# ADC.net
KiCad netlist of a schematic drawn in Altium Designer
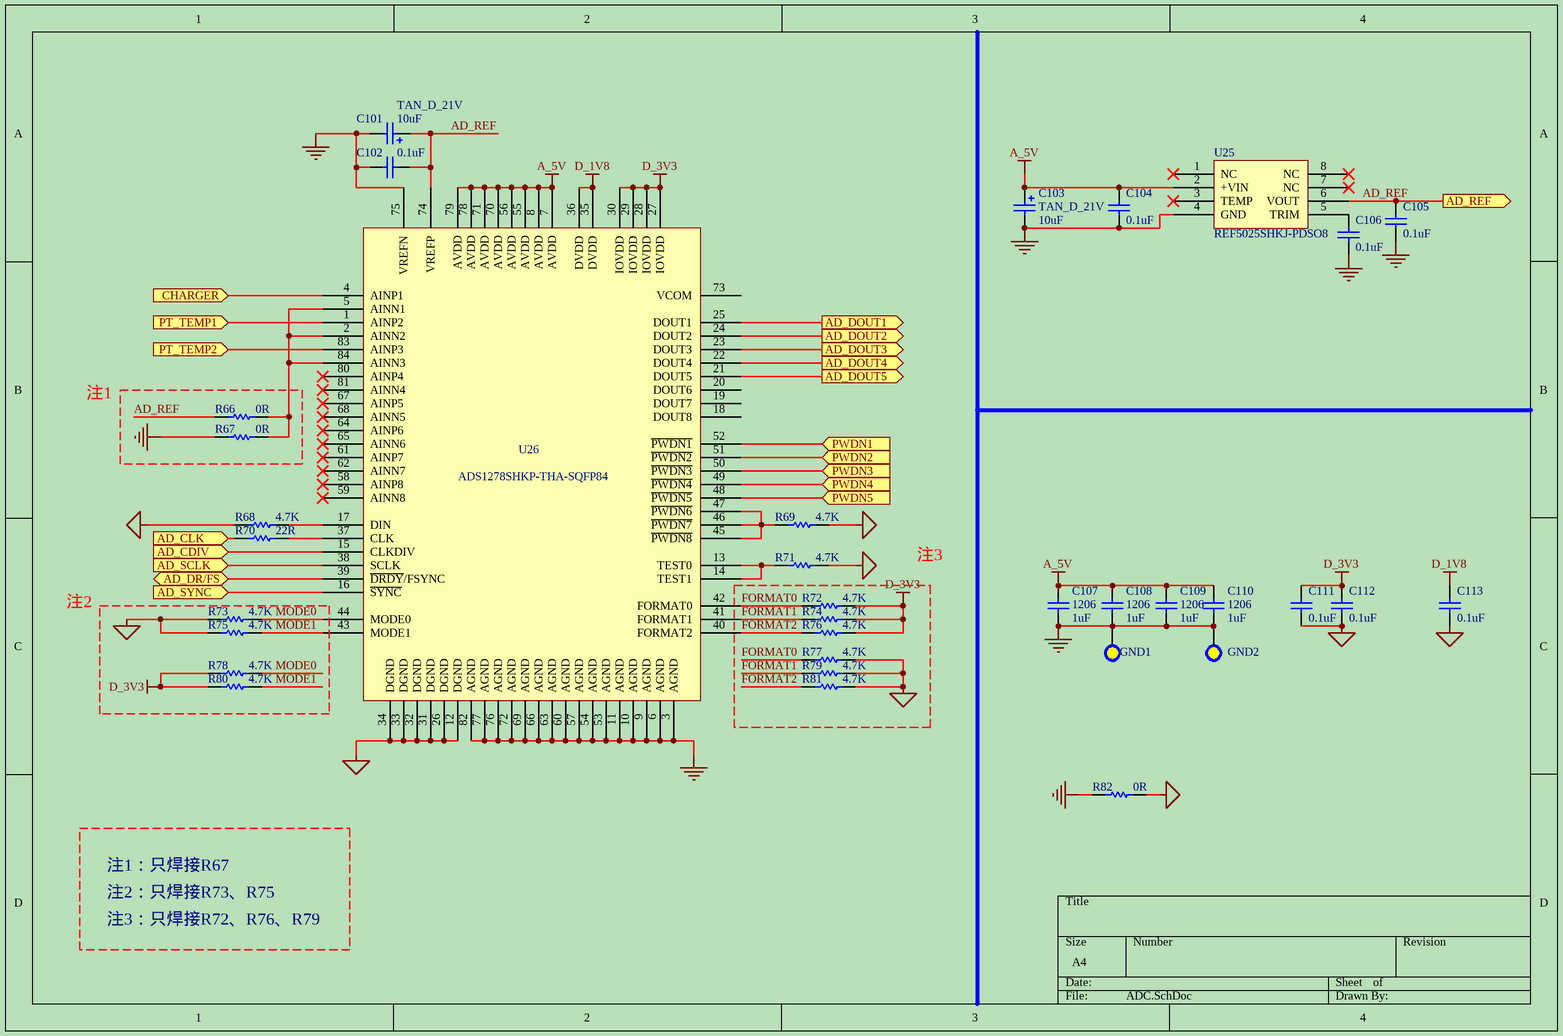
[diagram p0: ADC.SchDoc]

(export (version "E")
  (design (tool "Eeschema 10.0.6"))
  (components
    (comp (ref "C101")
      (value "TAN_D_21V")
      (footprint "EMRT MAIN CONTROLLER:CAPSP_2q2917")
      (description "Polarized Capacitor")
      (fields (field (name "ALTIUM_VALUE") "10uF") (field (name "PART NUMBER") "Y20024818"))
      (libsource (lib "电容") (part "Y20024818"))
    )
    (comp (ref "C102")
      (value "0.1uF")
      (footprint "CAPS0805_57")
      (description "Capacitor")
      (fields (field (name "PART NUMBER") "Y20025084") (field (name "Comment") "Cap"))
      (libsource (lib "Cap") (part "Cap"))
    )
    (comp (ref "C103")
      (value "TAN_D_21V")
      (footprint "EMRT MAIN CONTROLLER:CAPSP_2q2917")
      (description "Polarized Capacitor")
      (fields (field (name "ALTIUM_VALUE") "10uF") (field (name "PART NUMBER") "Y20024818"))
      (libsource (lib "电容") (part "Y20024818"))
    )
    (comp (ref "C104")
      (value "0.1uF")
      (footprint "CAPS0805_57")
      (description "Capacitor")
      (fields (field (name "PART NUMBER") "Y20025084") (field (name "Comment") "Cap"))
      (libsource (lib "Cap") (part "Cap"))
    )
    (comp (ref "C105")
      (value "0.1uF")
      (footprint "CAPS0805_57")
      (description "Capacitor")
      (fields (field (name "PART NUMBER") "Y20025084") (field (name "Comment") "Cap"))
      (libsource (lib "Cap") (part "Cap"))
    )
    (comp (ref "C106")
      (value "0.1uF")
      (footprint "CAPS0805_57")
      (description "Capacitor")
      (fields (field (name "PART NUMBER") "Y20025084") (field (name "Comment") "Cap"))
      (libsource (lib "Cap") (part "Cap"))
    )
    (comp (ref "C107")
      (value "1206")
      (footprint "CAPS1206_43")
      (description "Capacitor")
      (fields (field (name "ALTIUM_VALUE") "1uF") (field (name "PART NUMBER") "Y20024113"))
      (libsource (lib "Cap") (part "Cap"))
    )
    (comp (ref "C108")
      (value "1206")
      (footprint "CAPS1206_43")
      (description "Capacitor")
      (fields (field (name "ALTIUM_VALUE") "1uF") (field (name "PART NUMBER") "Y20024113"))
      (libsource (lib "Cap") (part "Cap"))
    )
    (comp (ref "C109")
      (value "1206")
      (footprint "CAPS1206_43")
      (description "Capacitor")
      (fields (field (name "ALTIUM_VALUE") "1uF") (field (name "PART NUMBER") "Y20024113"))
      (libsource (lib "Cap") (part "Cap"))
    )
    (comp (ref "C110")
      (value "1206")
      (footprint "CAPS1206_43")
      (description "Capacitor")
      (fields (field (name "ALTIUM_VALUE") "1uF") (field (name "PART NUMBER") "Y20024113"))
      (libsource (lib "Cap") (part "Cap"))
    )
    (comp (ref "C111")
      (value "0.1uF")
      (footprint "CAPS0805_57")
      (description "Capacitor")
      (fields (field (name "PART NUMBER") "Y20025084") (field (name "Comment") "Cap"))
      (libsource (lib "Cap") (part "Cap"))
    )
    (comp (ref "C112")
      (value "0.1uF")
      (footprint "CAPS0805_57")
      (description "Capacitor")
      (fields (field (name "PART NUMBER") "Y20025084") (field (name "Comment") "Cap"))
      (libsource (lib "Cap") (part "Cap"))
    )
    (comp (ref "C113")
      (value "0.1uF")
      (footprint "CAPS0805_57")
      (description "Capacitor")
      (fields (field (name "PART NUMBER") "Y20025084") (field (name "Comment") "Cap"))
      (libsource (lib "Cap") (part "Cap"))
    )
    (comp (ref "GND1")
      (value "TST_LARGE")
      (footprint "test_large")
      (libsource (lib "srj") (part "TEST_LARGE"))
    )
    (comp (ref "GND2")
      (value "TST_LARGE")
      (footprint "test_large")
      (libsource (lib "srj") (part "TEST_LARGE"))
    )
    (comp (ref "R66")
      (value "0R")
      (footprint "RESS0805")
      (description "Semiconductor Resistor")
      (fields
        (field (name "MANUFACTURER") "Generic Components")
        (field (name "Comment") "Res")
        (field (name "PUBLISHER") "Altium Hobart Technology Centre")
      )
      (libsource (lib "EMRT MAIN CONTROLLER") (part "Res"))
    )
    (comp (ref "R67")
      (value "0R")
      (footprint "RESS0805")
      (description "Semiconductor Resistor")
      (fields
        (field (name "MANUFACTURER") "Generic Components")
        (field (name "Comment") "Res")
        (field (name "PUBLISHER") "Altium Hobart Technology Centre")
      )
      (libsource (lib "EMRT MAIN CONTROLLER") (part "Res"))
    )
    (comp (ref "R68")
      (value "4.7K")
      (footprint "RESS0805")
      (description "Semiconductor Resistor")
      (fields
        (field (name "MANUFACTURER") "Generic Components")
        (field (name "Comment") "Res")
        (field (name "PUBLISHER") "Altium Hobart Technology Centre")
      )
      (libsource (lib "EMRT MAIN CONTROLLER") (part "Res"))
    )
    (comp (ref "R69")
      (value "4.7K")
      (footprint "RESS0805")
      (description "Semiconductor Resistor")
      (fields
        (field (name "MANUFACTURER") "Generic Components")
        (field (name "Comment") "Res")
        (field (name "PUBLISHER") "Altium Hobart Technology Centre")
      )
      (libsource (lib "EMRT MAIN CONTROLLER") (part "Res"))
    )
    (comp (ref "R70")
      (value "22R")
      (footprint "RESS0805")
      (description "Semiconductor Resistor")
      (fields
        (field (name "MANUFACTURER") "Generic Components")
        (field (name "Comment") "Res")
        (field (name "PUBLISHER") "Altium Hobart Technology Centre")
      )
      (libsource (lib "EMRT MAIN CONTROLLER") (part "Res"))
    )
    (comp (ref "R71")
      (value "4.7K")
      (footprint "RESS0805")
      (description "Semiconductor Resistor")
      (fields
        (field (name "MANUFACTURER") "Generic Components")
        (field (name "Comment") "Res")
        (field (name "PUBLISHER") "Altium Hobart Technology Centre")
      )
      (libsource (lib "EMRT MAIN CONTROLLER") (part "Res"))
    )
    (comp (ref "R72")
      (value "4.7K")
      (footprint "RESS0805")
      (description "Semiconductor Resistor")
      (fields
        (field (name "MANUFACTURER") "Generic Components")
        (field (name "Comment") "Res")
        (field (name "PUBLISHER") "Altium Hobart Technology Centre")
      )
      (libsource (lib "EMRT MAIN CONTROLLER") (part "Res"))
    )
    (comp (ref "R73")
      (value "4.7K")
      (footprint "RESS0805")
      (description "Semiconductor Resistor")
      (fields
        (field (name "MANUFACTURER") "Generic Components")
        (field (name "Comment") "Res")
        (field (name "PUBLISHER") "Altium Hobart Technology Centre")
      )
      (libsource (lib "EMRT MAIN CONTROLLER") (part "Res"))
    )
    (comp (ref "R74")
      (value "4.7K")
      (footprint "RESS0805")
      (description "Semiconductor Resistor")
      (fields
        (field (name "MANUFACTURER") "Generic Components")
        (field (name "Comment") "Res")
        (field (name "PUBLISHER") "Altium Hobart Technology Centre")
      )
      (libsource (lib "EMRT MAIN CONTROLLER") (part "Res"))
    )
    (comp (ref "R75")
      (value "4.7K")
      (footprint "RESS0805")
      (description "Semiconductor Resistor")
      (fields
        (field (name "MANUFACTURER") "Generic Components")
        (field (name "Comment") "Res")
        (field (name "PUBLISHER") "Altium Hobart Technology Centre")
      )
      (libsource (lib "EMRT MAIN CONTROLLER") (part "Res"))
    )
    (comp (ref "R76")
      (value "4.7K")
      (footprint "RESS0805")
      (description "Semiconductor Resistor")
      (fields
        (field (name "MANUFACTURER") "Generic Components")
        (field (name "Comment") "Res")
        (field (name "PUBLISHER") "Altium Hobart Technology Centre")
      )
      (libsource (lib "EMRT MAIN CONTROLLER") (part "Res"))
    )
    (comp (ref "R77")
      (value "4.7K")
      (footprint "RESS0805")
      (description "Semiconductor Resistor")
      (fields
        (field (name "MANUFACTURER") "Generic Components")
        (field (name "Comment") "Res")
        (field (name "PUBLISHER") "Altium Hobart Technology Centre")
      )
      (libsource (lib "EMRT MAIN CONTROLLER") (part "Res"))
    )
    (comp (ref "R78")
      (value "4.7K")
      (footprint "RESS0805")
      (description "Semiconductor Resistor")
      (fields
        (field (name "MANUFACTURER") "Generic Components")
        (field (name "Comment") "Res")
        (field (name "PUBLISHER") "Altium Hobart Technology Centre")
      )
      (libsource (lib "EMRT MAIN CONTROLLER") (part "Res"))
    )
    (comp (ref "R79")
      (value "4.7K")
      (footprint "RESS0805")
      (description "Semiconductor Resistor")
      (fields
        (field (name "MANUFACTURER") "Generic Components")
        (field (name "Comment") "Res")
        (field (name "PUBLISHER") "Altium Hobart Technology Centre")
      )
      (libsource (lib "EMRT MAIN CONTROLLER") (part "Res"))
    )
    (comp (ref "R80")
      (value "4.7K")
      (footprint "RESS0805")
      (description "Semiconductor Resistor")
      (fields
        (field (name "MANUFACTURER") "Generic Components")
        (field (name "Comment") "Res")
        (field (name "PUBLISHER") "Altium Hobart Technology Centre")
      )
      (libsource (lib "EMRT MAIN CONTROLLER") (part "Res"))
    )
    (comp (ref "R81")
      (value "4.7K")
      (footprint "RESS0805")
      (description "Semiconductor Resistor")
      (fields
        (field (name "MANUFACTURER") "Generic Components")
        (field (name "Comment") "Res")
        (field (name "PUBLISHER") "Altium Hobart Technology Centre")
      )
      (libsource (lib "EMRT MAIN CONTROLLER") (part "Res"))
    )
    (comp (ref "R82")
      (value "0R")
      (footprint "RESS0805")
      (description "Semiconductor Resistor")
      (fields
        (field (name "MANUFACTURER") "Generic Components")
        (field (name "Comment") "Res")
        (field (name "PUBLISHER") "Altium Hobart Technology Centre")
      )
      (libsource (lib "EMRT MAIN CONTROLLER") (part "Res"))
    )
    (comp (ref "U25")
      (value "REF5025SHKJ-PDSO8")
      (footprint "PDSO8")
      (libsource (lib "srj") (part "REF5025ID"))
    )
    (comp (ref "U26")
      (value "ADS1278SHKP-THA-SQFP84")
      (footprint "HB-CQFP_84q1933×1933×280_p50 - duplicate")
      (libsource (lib "MC-HT") (part "ADS1278SHFQ"))
    )
  )
  (nets
    (net (code "1") (name "/AD_CDIV") (class "Default")
      (node (ref "U26") (pin "15") (pinfunction "CLKDIV_15") (pintype "passive"))
    )
    (net (code "2") (name "/AD_CLK") (class "Default")
      (node (ref "R70") (pin "2") (pinfunction "2_2") (pintype "passive"))
    )
    (net (code "3") (name "/AD_DOUT1") (class "Default")
      (node (ref "U26") (pin "25") (pinfunction "DOUT1_25") (pintype "passive"))
    )
    (net (code "4") (name "/AD_DOUT2") (class "Default")
      (node (ref "U26") (pin "24") (pinfunction "DOUT2_24") (pintype "passive"))
    )
    (net (code "5") (name "/AD_DOUT3") (class "Default")
      (node (ref "U26") (pin "23") (pinfunction "DOUT3_23") (pintype "passive"))
    )
    (net (code "6") (name "/AD_DOUT4") (class "Default")
      (node (ref "U26") (pin "22") (pinfunction "DOUT4_22") (pintype "passive"))
    )
    (net (code "7") (name "/AD_DOUT5") (class "Default")
      (node (ref "U26") (pin "21") (pinfunction "DOUT5_21") (pintype "passive"))
    )
    (net (code "8") (name "/AD_DR{slash}FS") (class "Default")
      (node (ref "U26") (pin "39") (pinfunction "~{DRDY}/FSYNC_39") (pintype "passive"))
    )
    (net (code "9") (name "/AD_REF") (class "Default")
      (node (ref "C101") (pin "1") (pinfunction "1_1") (pintype "passive"))
      (node (ref "C102") (pin "1") (pinfunction "1_1") (pintype "passive"))
      (node (ref "C105") (pin "2") (pinfunction "2_2") (pintype "passive"))
      (node (ref "R66") (pin "2") (pinfunction "2_2") (pintype "passive"))
      (node (ref "U25") (pin "6") (pinfunction "VOUT_6") (pintype "passive"))
      (node (ref "U26") (pin "74") (pinfunction "VREFP_74") (pintype "passive"))
    )
    (net (code "10") (name "/AD_SCLK") (class "Default")
      (node (ref "U26") (pin "38") (pinfunction "SCLK_38") (pintype "passive"))
    )
    (net (code "11") (name "/AD_SYNC") (class "Default")
      (node (ref "U26") (pin "16") (pinfunction "~{SYNC}_16") (pintype "passive"))
    )
    (net (code "12") (name "/CHARGER") (class "Default")
      (node (ref "U26") (pin "4") (pinfunction "AINP1_4") (pintype "passive"))
    )
    (net (code "13") (name "/FORMAT0") (class "Default")
      (node (ref "R72") (pin "2") (pinfunction "2_2") (pintype "passive"))
      (node (ref "R77") (pin "2") (pinfunction "2_2") (pintype "passive"))
      (node (ref "U26") (pin "42") (pinfunction "FORMAT0_42") (pintype "passive"))
    )
    (net (code "14") (name "/FORMAT1") (class "Default")
      (node (ref "R74") (pin "2") (pinfunction "2_2") (pintype "passive"))
      (node (ref "R79") (pin "2") (pinfunction "2_2") (pintype "passive"))
      (node (ref "U26") (pin "41") (pinfunction "FORMAT1_41") (pintype "passive"))
    )
    (net (code "15") (name "/FORMAT2") (class "Default")
      (node (ref "R76") (pin "2") (pinfunction "2_2") (pintype "passive"))
      (node (ref "R81") (pin "2") (pinfunction "2_2") (pintype "passive"))
      (node (ref "U26") (pin "40") (pinfunction "FORMAT2_40") (pintype "passive"))
    )
    (net (code "16") (name "/MODE0") (class "Default")
      (node (ref "R73") (pin "1") (pinfunction "1_1") (pintype "passive"))
      (node (ref "R78") (pin "1") (pinfunction "1_1") (pintype "passive"))
      (node (ref "U26") (pin "44") (pinfunction "MODE0_44") (pintype "passive"))
    )
    (net (code "17") (name "/MODE1") (class "Default")
      (node (ref "R75") (pin "1") (pinfunction "1_1") (pintype "passive"))
      (node (ref "R80") (pin "1") (pinfunction "1_1") (pintype "passive"))
      (node (ref "U26") (pin "43") (pinfunction "MODE1_43") (pintype "passive"))
    )
    (net (code "18") (name "/PT_TEMP1") (class "Default")
      (node (ref "U26") (pin "1") (pinfunction "AINP2_1") (pintype "passive"))
    )
    (net (code "19") (name "/PT_TEMP2") (class "Default")
      (node (ref "U26") (pin "83") (pinfunction "AINP3_83") (pintype "passive"))
    )
    (net (code "20") (name "/PWDN1") (class "Default")
      (node (ref "U26") (pin "52") (pinfunction "~{PWDN1}_52") (pintype "passive"))
    )
    (net (code "21") (name "/PWDN2") (class "Default")
      (node (ref "U26") (pin "51") (pinfunction "~{PWDN2}_51") (pintype "passive"))
    )
    (net (code "22") (name "/PWDN3") (class "Default")
      (node (ref "U26") (pin "50") (pinfunction "~{PWDN3}_50") (pintype "passive"))
    )
    (net (code "23") (name "/PWDN4") (class "Default")
      (node (ref "U26") (pin "49") (pinfunction "~{PWDN4}_49") (pintype "passive"))
    )
    (net (code "24") (name "/PWDN5") (class "Default")
      (node (ref "U26") (pin "48") (pinfunction "~{PWDN5}_48") (pintype "passive"))
    )
    (net (code "25") (name "A_5V") (class "Default")
      (node (ref "C103") (pin "1") (pinfunction "1_1") (pintype "passive"))
      (node (ref "C104") (pin "2") (pinfunction "2_2") (pintype "passive"))
      (node (ref "C107") (pin "2") (pinfunction "2_2") (pintype "passive"))
      (node (ref "C108") (pin "2") (pinfunction "2_2") (pintype "passive"))
      (node (ref "C109") (pin "2") (pinfunction "2_2") (pintype "passive"))
      (node (ref "C110") (pin "2") (pinfunction "2_2") (pintype "passive"))
      (node (ref "U25") (pin "2") (pinfunction "+VIN_2") (pintype "passive"))
      (node (ref "U26") (pin "55") (pinfunction "AVDD_55") (pintype "passive"))
      (node (ref "U26") (pin "56") (pinfunction "AVDD_56") (pintype "passive"))
      (node (ref "U26") (pin "7") (pinfunction "AVDD_7") (pintype "passive"))
      (node (ref "U26") (pin "70") (pinfunction "AVDD_70") (pintype "passive"))
      (node (ref "U26") (pin "71") (pinfunction "AVDD_71") (pintype "passive"))
      (node (ref "U26") (pin "78") (pinfunction "AVDD_78") (pintype "passive"))
      (node (ref "U26") (pin "79") (pinfunction "AVDD_79") (pintype "passive"))
      (node (ref "U26") (pin "8") (pinfunction "AVDD_8") (pintype "passive"))
    )
    (net (code "26") (name "DGND") (class "Default")
      (node (ref "C111") (pin "1") (pinfunction "1_1") (pintype "passive"))
      (node (ref "C112") (pin "1") (pinfunction "1_1") (pintype "passive"))
      (node (ref "C113") (pin "1") (pinfunction "1_1") (pintype "passive"))
      (node (ref "R68") (pin "2") (pinfunction "2_2") (pintype "passive"))
      (node (ref "R69") (pin "1") (pinfunction "1_1") (pintype "passive"))
      (node (ref "R71") (pin "1") (pinfunction "1_1") (pintype "passive"))
      (node (ref "R73") (pin "2") (pinfunction "2_2") (pintype "passive"))
      (node (ref "R75") (pin "2") (pinfunction "2_2") (pintype "passive"))
      (node (ref "R77") (pin "1") (pinfunction "1_1") (pintype "passive"))
      (node (ref "R79") (pin "1") (pinfunction "1_1") (pintype "passive"))
      (node (ref "R81") (pin "1") (pinfunction "1_1") (pintype "passive"))
      (node (ref "R82") (pin "1") (pinfunction "1_1") (pintype "passive"))
      (node (ref "U26") (pin "12") (pinfunction "DGND_12") (pintype "passive"))
      (node (ref "U26") (pin "26") (pinfunction "DGND_26") (pintype "passive"))
      (node (ref "U26") (pin "31") (pinfunction "DGND_31") (pintype "passive"))
      (node (ref "U26") (pin "32") (pinfunction "DGND_32") (pintype "passive"))
      (node (ref "U26") (pin "33") (pinfunction "DGND_33") (pintype "passive"))
      (node (ref "U26") (pin "34") (pinfunction "DGND_34") (pintype "passive"))
    )
    (net (code "27") (name "D_1V8") (class "Default")
      (node (ref "C113") (pin "2") (pinfunction "2_2") (pintype "passive"))
      (node (ref "U26") (pin "35") (pinfunction "DVDD_35") (pintype "passive"))
      (node (ref "U26") (pin "36") (pinfunction "DVDD_36") (pintype "passive"))
    )
    (net (code "28") (name "D_3V3") (class "Default")
      (node (ref "C111") (pin "2") (pinfunction "2_2") (pintype "passive"))
      (node (ref "C112") (pin "2") (pinfunction "2_2") (pintype "passive"))
      (node (ref "R72") (pin "1") (pinfunction "1_1") (pintype "passive"))
      (node (ref "R74") (pin "1") (pinfunction "1_1") (pintype "passive"))
      (node (ref "R76") (pin "1") (pinfunction "1_1") (pintype "passive"))
      (node (ref "R78") (pin "2") (pinfunction "2_2") (pintype "passive"))
      (node (ref "R80") (pin "2") (pinfunction "2_2") (pintype "passive"))
      (node (ref "U26") (pin "27") (pinfunction "IOVDD_27") (pintype "passive"))
      (node (ref "U26") (pin "28") (pinfunction "IOVDD_28") (pintype "passive"))
      (node (ref "U26") (pin "29") (pinfunction "IOVDD_29") (pintype "passive"))
      (node (ref "U26") (pin "30") (pinfunction "IOVDD_30") (pintype "passive"))
    )
    (net (code "29") (name "GND") (class "Default")
      (node (ref "C101") (pin "2") (pinfunction "2_2") (pintype "passive"))
      (node (ref "C102") (pin "2") (pinfunction "2_2") (pintype "passive"))
      (node (ref "C103") (pin "2") (pinfunction "2_2") (pintype "passive"))
      (node (ref "C104") (pin "1") (pinfunction "1_1") (pintype "passive"))
      (node (ref "C105") (pin "1") (pinfunction "1_1") (pintype "passive"))
      (node (ref "C106") (pin "1") (pinfunction "1_1") (pintype "passive"))
      (node (ref "C107") (pin "1") (pinfunction "1_1") (pintype "passive"))
      (node (ref "C108") (pin "1") (pinfunction "1_1") (pintype "passive"))
      (node (ref "C109") (pin "1") (pinfunction "1_1") (pintype "passive"))
      (node (ref "C110") (pin "1") (pinfunction "1_1") (pintype "passive"))
      (node (ref "GND1") (pin "1") (pinfunction "1_1") (pintype "passive"))
      (node (ref "GND2") (pin "1") (pinfunction "1_1") (pintype "passive"))
      (node (ref "R67") (pin "2") (pinfunction "2_2") (pintype "passive"))
      (node (ref "R82") (pin "2") (pinfunction "2_2") (pintype "passive"))
      (node (ref "U25") (pin "4") (pinfunction "GND_4") (pintype "passive"))
      (node (ref "U26") (pin "10") (pinfunction "AGND_10") (pintype "passive"))
      (node (ref "U26") (pin "11") (pinfunction "AGND_11") (pintype "passive"))
      (node (ref "U26") (pin "3") (pinfunction "AGND_3") (pintype "passive"))
      (node (ref "U26") (pin "53") (pinfunction "AGND_53") (pintype "passive"))
      (node (ref "U26") (pin "54") (pinfunction "AGND_54") (pintype "passive"))
      (node (ref "U26") (pin "57") (pinfunction "AGND_57") (pintype "passive"))
      (node (ref "U26") (pin "6") (pinfunction "AGND_6") (pintype "passive"))
      (node (ref "U26") (pin "60") (pinfunction "AGND_60") (pintype "passive"))
      (node (ref "U26") (pin "63") (pinfunction "AGND_63") (pintype "passive"))
      (node (ref "U26") (pin "66") (pinfunction "AGND_66") (pintype "passive"))
      (node (ref "U26") (pin "69") (pinfunction "AGND_69") (pintype "passive"))
      (node (ref "U26") (pin "72") (pinfunction "AGND_72") (pintype "passive"))
      (node (ref "U26") (pin "75") (pinfunction "VREFN_75") (pintype "passive"))
      (node (ref "U26") (pin "76") (pinfunction "AGND_76") (pintype "passive"))
      (node (ref "U26") (pin "77") (pinfunction "AGND_77") (pintype "passive"))
      (node (ref "U26") (pin "82") (pinfunction "AGND_82") (pintype "passive"))
      (node (ref "U26") (pin "9") (pinfunction "AGND_9") (pintype "passive"))
    )
    (net (code "30") (name "Net-(U25-TRIM)") (class "Default")
      (node (ref "C106") (pin "2") (pinfunction "2_2") (pintype "passive"))
      (node (ref "U25") (pin "5") (pinfunction "TRIM_5") (pintype "passive"))
    )
    (net (code "31") (name "Net-(U26-AINN1)") (class "Default")
      (node (ref "R66") (pin "1") (pinfunction "1_1") (pintype "passive"))
      (node (ref "R67") (pin "1") (pinfunction "1_1") (pintype "passive"))
      (node (ref "U26") (pin "2") (pinfunction "AINN2_2") (pintype "passive"))
      (node (ref "U26") (pin "5") (pinfunction "AINN1_5") (pintype "passive"))
      (node (ref "U26") (pin "84") (pinfunction "AINN3_84") (pintype "passive"))
    )
    (net (code "32") (name "Net-(U26-CLK)") (class "Default")
      (node (ref "R70") (pin "1") (pinfunction "1_1") (pintype "passive"))
      (node (ref "U26") (pin "37") (pinfunction "CLK_37") (pintype "passive"))
    )
    (net (code "33") (name "Net-(U26-DIN)") (class "Default")
      (node (ref "R68") (pin "1") (pinfunction "1_1") (pintype "passive"))
      (node (ref "U26") (pin "17") (pinfunction "DIN_17") (pintype "passive"))
    )
    (net (code "34") (name "Net-(U26-TEST0)") (class "Default")
      (node (ref "R71") (pin "2") (pinfunction "2_2") (pintype "passive"))
      (node (ref "U26") (pin "13") (pinfunction "TEST0_13") (pintype "passive"))
      (node (ref "U26") (pin "14") (pinfunction "TEST1_14") (pintype "passive"))
    )
    (net (code "35") (name "Net-(U26-~{PWDN6})") (class "Default")
      (node (ref "R69") (pin "2") (pinfunction "2_2") (pintype "passive"))
      (node (ref "U26") (pin "45") (pinfunction "~{PWDN8}_45") (pintype "passive"))
      (node (ref "U26") (pin "46") (pinfunction "~{PWDN7}_46") (pintype "passive"))
      (node (ref "U26") (pin "47") (pinfunction "~{PWDN6}_47") (pintype "passive"))
    )
    (net (code "36") (name "unconnected-(U25-NC-Pad1)") (class "Default")
      (node (ref "U25") (pin "1") (pinfunction "NC_1") (pintype "passive+no_connect"))
    )
    (net (code "37") (name "unconnected-(U25-NC-Pad7)") (class "Default")
      (node (ref "U25") (pin "7") (pinfunction "NC_7") (pintype "passive+no_connect"))
    )
    (net (code "38") (name "unconnected-(U25-NC-Pad8)") (class "Default")
      (node (ref "U25") (pin "8") (pinfunction "NC_8") (pintype "passive+no_connect"))
    )
    (net (code "39") (name "unconnected-(U25-TEMP-Pad3)") (class "Default")
      (node (ref "U25") (pin "3") (pinfunction "TEMP_3") (pintype "passive+no_connect"))
    )
    (net (code "40") (name "unconnected-(U26-AINN4-Pad81)") (class "Default")
      (node (ref "U26") (pin "81") (pinfunction "AINN4_81") (pintype "passive+no_connect"))
    )
    (net (code "41") (name "unconnected-(U26-AINN5-Pad68)") (class "Default")
      (node (ref "U26") (pin "68") (pinfunction "AINN5_68") (pintype "passive+no_connect"))
    )
    (net (code "42") (name "unconnected-(U26-AINN6-Pad65)") (class "Default")
      (node (ref "U26") (pin "65") (pinfunction "AINN6_65") (pintype "passive+no_connect"))
    )
    (net (code "43") (name "unconnected-(U26-AINN7-Pad62)") (class "Default")
      (node (ref "U26") (pin "62") (pinfunction "AINN7_62") (pintype "passive+no_connect"))
    )
    (net (code "44") (name "unconnected-(U26-AINN8-Pad59)") (class "Default")
      (node (ref "U26") (pin "59") (pinfunction "AINN8_59") (pintype "passive+no_connect"))
    )
    (net (code "45") (name "unconnected-(U26-AINP4-Pad80)") (class "Default")
      (node (ref "U26") (pin "80") (pinfunction "AINP4_80") (pintype "passive+no_connect"))
    )
    (net (code "46") (name "unconnected-(U26-AINP5-Pad67)") (class "Default")
      (node (ref "U26") (pin "67") (pinfunction "AINP5_67") (pintype "passive+no_connect"))
    )
    (net (code "47") (name "unconnected-(U26-AINP6-Pad64)") (class "Default")
      (node (ref "U26") (pin "64") (pinfunction "AINP6_64") (pintype "passive+no_connect"))
    )
    (net (code "48") (name "unconnected-(U26-AINP7-Pad61)") (class "Default")
      (node (ref "U26") (pin "61") (pinfunction "AINP7_61") (pintype "passive+no_connect"))
    )
    (net (code "49") (name "unconnected-(U26-AINP8-Pad58)") (class "Default")
      (node (ref "U26") (pin "58") (pinfunction "AINP8_58") (pintype "passive+no_connect"))
    )
    (net (code "50") (name "unconnected-(U26-DOUT6-Pad20)") (class "Default")
      (node (ref "U26") (pin "20") (pinfunction "DOUT6_20") (pintype "passive"))
    )
    (net (code "51") (name "unconnected-(U26-DOUT7-Pad19)") (class "Default")
      (node (ref "U26") (pin "19") (pinfunction "DOUT7_19") (pintype "passive"))
    )
    (net (code "52") (name "unconnected-(U26-DOUT8-Pad18)") (class "Default")
      (node (ref "U26") (pin "18") (pinfunction "DOUT8_18") (pintype "passive"))
    )
    (net (code "53") (name "unconnected-(U26-VCOM-Pad73)") (class "Default")
      (node (ref "U26") (pin "73") (pinfunction "VCOM_73") (pintype "passive"))
    )
  )
)
